# nRF24L01_SMD_0603.net
KiCad netlist of a schematic drawn in EAGLE
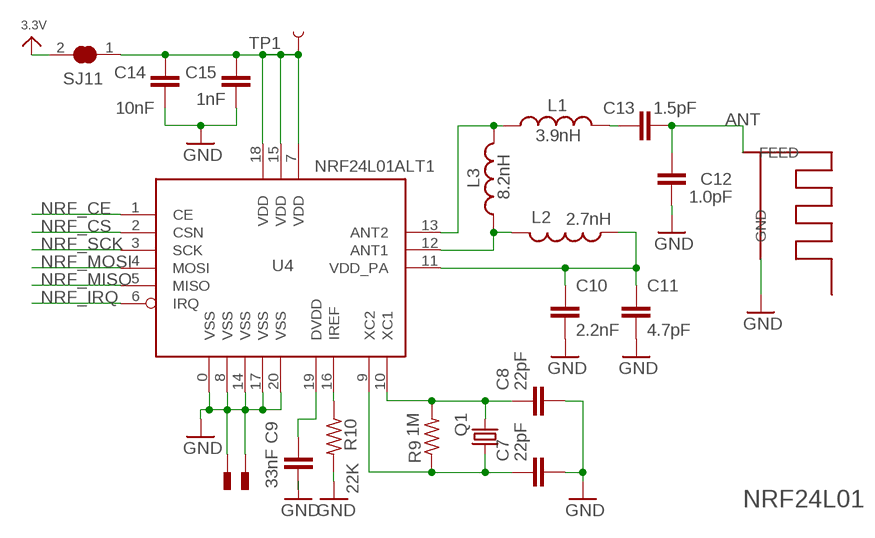
[diagram p0: schematic, sheet 1]

(export (version "E")
  (design (tool "Eeschema 10.0.6"))
  (components
    (comp (ref "ANT2")
      (value "NRF24L01_ANTENNA")
      (footprint "eagle-import:NRF24L01_ANT")
      (libsource (lib "eagle-import") (part "NRF24L01_ANTENNA"))
    )
    (comp (ref "C7")
      (value "22pF")
      (footprint "eagle-import:C0603")
      (libsource (lib "eagle-import") (part "C-EUC0603"))
    )
    (comp (ref "C8")
      (value "22pF")
      (footprint "eagle-import:C0603")
      (libsource (lib "eagle-import") (part "C-EUC0603"))
    )
    (comp (ref "C9")
      (value "33nF")
      (footprint "eagle-import:C0603")
      (libsource (lib "eagle-import") (part "C-EUC0603"))
    )
    (comp (ref "C10")
      (value "2.2nF")
      (footprint "eagle-import:C0603")
      (libsource (lib "eagle-import") (part "C-EUC0603"))
    )
    (comp (ref "C11")
      (value "4.7pF")
      (footprint "eagle-import:C0603")
      (libsource (lib "eagle-import") (part "C-EUC0603"))
    )
    (comp (ref "C12")
      (value "1.0pF")
      (footprint "eagle-import:C0603")
      (libsource (lib "eagle-import") (part "C-EUC0603"))
    )
    (comp (ref "C13")
      (value "1.5pF")
      (footprint "eagle-import:C0603")
      (libsource (lib "eagle-import") (part "C-EUC0603"))
    )
    (comp (ref "C14")
      (value "10nF")
      (footprint "eagle-import:C0603")
      (libsource (lib "eagle-import") (part "C-EUC0603"))
    )
    (comp (ref "C15")
      (value "1nF")
      (footprint "eagle-import:C0603")
      (libsource (lib "eagle-import") (part "C-EUC0603"))
    )
    (comp (ref "L1")
      (value "3.9nH")
      (footprint "eagle-import:L0603")
      (libsource (lib "eagle-import") (part "L-USL0603"))
    )
    (comp (ref "L2")
      (value "2.7nH")
      (footprint "eagle-import:L0603")
      (libsource (lib "eagle-import") (part "L-USL0603"))
    )
    (comp (ref "L3")
      (value "8.2nH")
      (footprint "eagle-import:L0603")
      (libsource (lib "eagle-import") (part "L-USL0603"))
    )
    (comp (ref "Q1")
      (value "KX-7")
      (footprint "eagle-import:3.2X2.5_KX-7")
      (libsource (lib "eagle-import") (part "KX-7"))
    )
    (comp (ref "R9")
      (value "1M")
      (footprint "eagle-import:R0603")
      (libsource (lib "eagle-import") (part "R-US_R0603"))
    )
    (comp (ref "R10")
      (value "22K")
      (footprint "eagle-import:R0603")
      (libsource (lib "eagle-import") (part "R-US_R0603"))
    )
    (comp (ref "SJ11")
      (value "SOLDERJUMPER_CLOSED")
      (footprint "eagle-import:SOLDERJUMPER_CLOSEDWIRE")
      (libsource (lib "eagle-import") (part "SOLDERJUMPER_CLOSED"))
    )
    (comp (ref "TP1")
      (value "TEST-POINT3X5")
      (footprint "eagle-import:PAD.03X.05")
      (libsource (lib "eagle-import") (part "TEST-POINT3X5"))
    )
    (comp (ref "U$27")
      (value "PAD")
      (footprint "eagle-import:PAD-0.008")
      (libsource (lib "eagle-import") (part "PAD"))
    )
    (comp (ref "U$28")
      (value "PAD")
      (footprint "eagle-import:PAD-0.008")
      (libsource (lib "eagle-import") (part "PAD"))
    )
    (comp (ref "U4")
      (value "NRF24L01ALT1")
      (footprint "eagle-import:QFN20_ALT1")
      (libsource (lib "eagle-import") (part "NRF24L01ALT1"))
    )
  )
  (nets
    (net (code "1") (name "/ANT") (class "Default")
      (node (ref "ANT2") (pin "FEED") (pinfunction "FEED_FEED") (pintype "bidirectional"))
      (node (ref "C12") (pin "2") (pinfunction "2_2") (pintype "passive"))
      (node (ref "C13") (pin "2") (pinfunction "2_2") (pintype "passive"))
    )
    (net (code "2") (name "/NRF_CE") (class "Default")
      (node (ref "U4") (pin "1") (pinfunction "CE_1") (pintype "input"))
    )
    (net (code "3") (name "/NRF_CS") (class "Default")
      (node (ref "U4") (pin "2") (pinfunction "CSN_2") (pintype "input"))
    )
    (net (code "4") (name "/NRF_IRQ") (class "Default")
      (node (ref "U4") (pin "6") (pinfunction "IRQ_6") (pintype "output"))
    )
    (net (code "5") (name "/NRF_MISO") (class "Default")
      (node (ref "U4") (pin "5") (pinfunction "MISO_5") (pintype "output"))
    )
    (net (code "6") (name "/NRF_MOSI") (class "Default")
      (node (ref "U4") (pin "4") (pinfunction "MOSI_4") (pintype "input"))
    )
    (net (code "7") (name "/NRF_SCK") (class "Default")
      (node (ref "U4") (pin "3") (pinfunction "SCK_3") (pintype "input"))
    )
    (net (code "8") (name "3.3V") (class "Default")
      (node (ref "SJ11") (pin "2") (pinfunction "2_2") (pintype "passive"))
    )
    (net (code "9") (name "GND") (class "Default")
      (node (ref "ANT2") (pin "GND") (pinfunction "GND_GND") (pintype "bidirectional"))
      (node (ref "C10") (pin "2") (pinfunction "2_2") (pintype "passive"))
      (node (ref "C11") (pin "2") (pinfunction "2_2") (pintype "passive"))
      (node (ref "C12") (pin "1") (pinfunction "1_1") (pintype "passive"))
      (node (ref "C14") (pin "1") (pinfunction "1_1") (pintype "passive"))
      (node (ref "C15") (pin "1") (pinfunction "1_1") (pintype "passive"))
      (node (ref "C7") (pin "2") (pinfunction "2_2") (pintype "passive"))
      (node (ref "C8") (pin "2") (pinfunction "2_2") (pintype "passive"))
      (node (ref "C9") (pin "2") (pinfunction "2_2") (pintype "passive"))
      (node (ref "R10") (pin "2") (pinfunction "2_2") (pintype "passive"))
      (node (ref "U$27") (pin "P$1") (pinfunction "P$1_P$1") (pintype "bidirectional"))
      (node (ref "U$28") (pin "P$1") (pinfunction "P$1_P$1") (pintype "bidirectional"))
      (node (ref "U4") (pin "0") (pinfunction "VSS_0") (pintype "power_in"))
      (node (ref "U4") (pin "14") (pinfunction "VSS_14") (pintype "power_in"))
      (node (ref "U4") (pin "17") (pinfunction "VSS_17") (pintype "power_in"))
      (node (ref "U4") (pin "20") (pinfunction "VSS_20") (pintype "power_in"))
      (node (ref "U4") (pin "8") (pinfunction "VSS_8") (pintype "power_in"))
    )
    (net (code "10") (name "Net-(C13-Pad1)") (class "Default")
      (node (ref "C13") (pin "1") (pinfunction "1_1") (pintype "passive"))
      (node (ref "L1") (pin "2") (pinfunction "2_2") (pintype "passive"))
    )
    (net (code "11") (name "Net-(Q1-2)") (class "Default")
      (node (ref "C8") (pin "1") (pinfunction "1_1") (pintype "passive"))
      (node (ref "Q1") (pin "3") (pinfunction "2_3") (pintype "passive"))
      (node (ref "R9") (pin "2") (pinfunction "2_2") (pintype "passive"))
      (node (ref "U4") (pin "10") (pinfunction "XC1_10") (pintype "input"))
    )
    (net (code "12") (name "Net-(TP1-1)") (class "Default")
      (node (ref "C14") (pin "2") (pinfunction "2_2") (pintype "passive"))
      (node (ref "C15") (pin "2") (pinfunction "2_2") (pintype "passive"))
      (node (ref "SJ11") (pin "1") (pinfunction "1_1") (pintype "passive"))
      (node (ref "TP1") (pin "P$1") (pinfunction "1_P$1") (pintype "bidirectional"))
      (node (ref "U4") (pin "15") (pinfunction "VDD_15") (pintype "power_in"))
      (node (ref "U4") (pin "18") (pinfunction "VDD_18") (pintype "power_in"))
      (node (ref "U4") (pin "7") (pinfunction "VDD_7") (pintype "power_in"))
    )
    (net (code "13") (name "Net-(U4-ANT1)") (class "Default")
      (node (ref "L2") (pin "2") (pinfunction "2_2") (pintype "passive"))
      (node (ref "L3") (pin "1") (pinfunction "1_1") (pintype "passive"))
      (node (ref "U4") (pin "12") (pinfunction "ANT1_12") (pintype "output"))
    )
    (net (code "14") (name "Net-(U4-ANT2)") (class "Default")
      (node (ref "L1") (pin "1") (pinfunction "1_1") (pintype "passive"))
      (node (ref "L3") (pin "2") (pinfunction "2_2") (pintype "passive"))
      (node (ref "U4") (pin "13") (pinfunction "ANT2_13") (pintype "output"))
    )
    (net (code "15") (name "Net-(U4-DVDD)") (class "Default")
      (node (ref "C9") (pin "1") (pinfunction "1_1") (pintype "passive"))
      (node (ref "U4") (pin "19") (pinfunction "DVDD_19") (pintype "power_in"))
    )
    (net (code "16") (name "Net-(U4-IREF)") (class "Default")
      (node (ref "R10") (pin "1") (pinfunction "1_1") (pintype "passive"))
      (node (ref "U4") (pin "16") (pinfunction "IREF_16") (pintype "input"))
    )
    (net (code "17") (name "Net-(U4-VDD_PA)") (class "Default")
      (node (ref "C10") (pin "1") (pinfunction "1_1") (pintype "passive"))
      (node (ref "C11") (pin "1") (pinfunction "1_1") (pintype "passive"))
      (node (ref "L2") (pin "1") (pinfunction "1_1") (pintype "passive"))
      (node (ref "U4") (pin "11") (pinfunction "VDD_PA_11") (pintype "power_in"))
    )
    (net (code "18") (name "Net-(U4-XC2)") (class "Default")
      (node (ref "C7") (pin "1") (pinfunction "1_1") (pintype "passive"))
      (node (ref "Q1") (pin "1") (pinfunction "1_1") (pintype "passive"))
      (node (ref "R9") (pin "1") (pinfunction "1_1") (pintype "passive"))
      (node (ref "U4") (pin "9") (pinfunction "XC2_9") (pintype "input"))
    )
  )
)
